# Current_measurement.net
KiCad netlist of a schematic drawn in Altium Designer
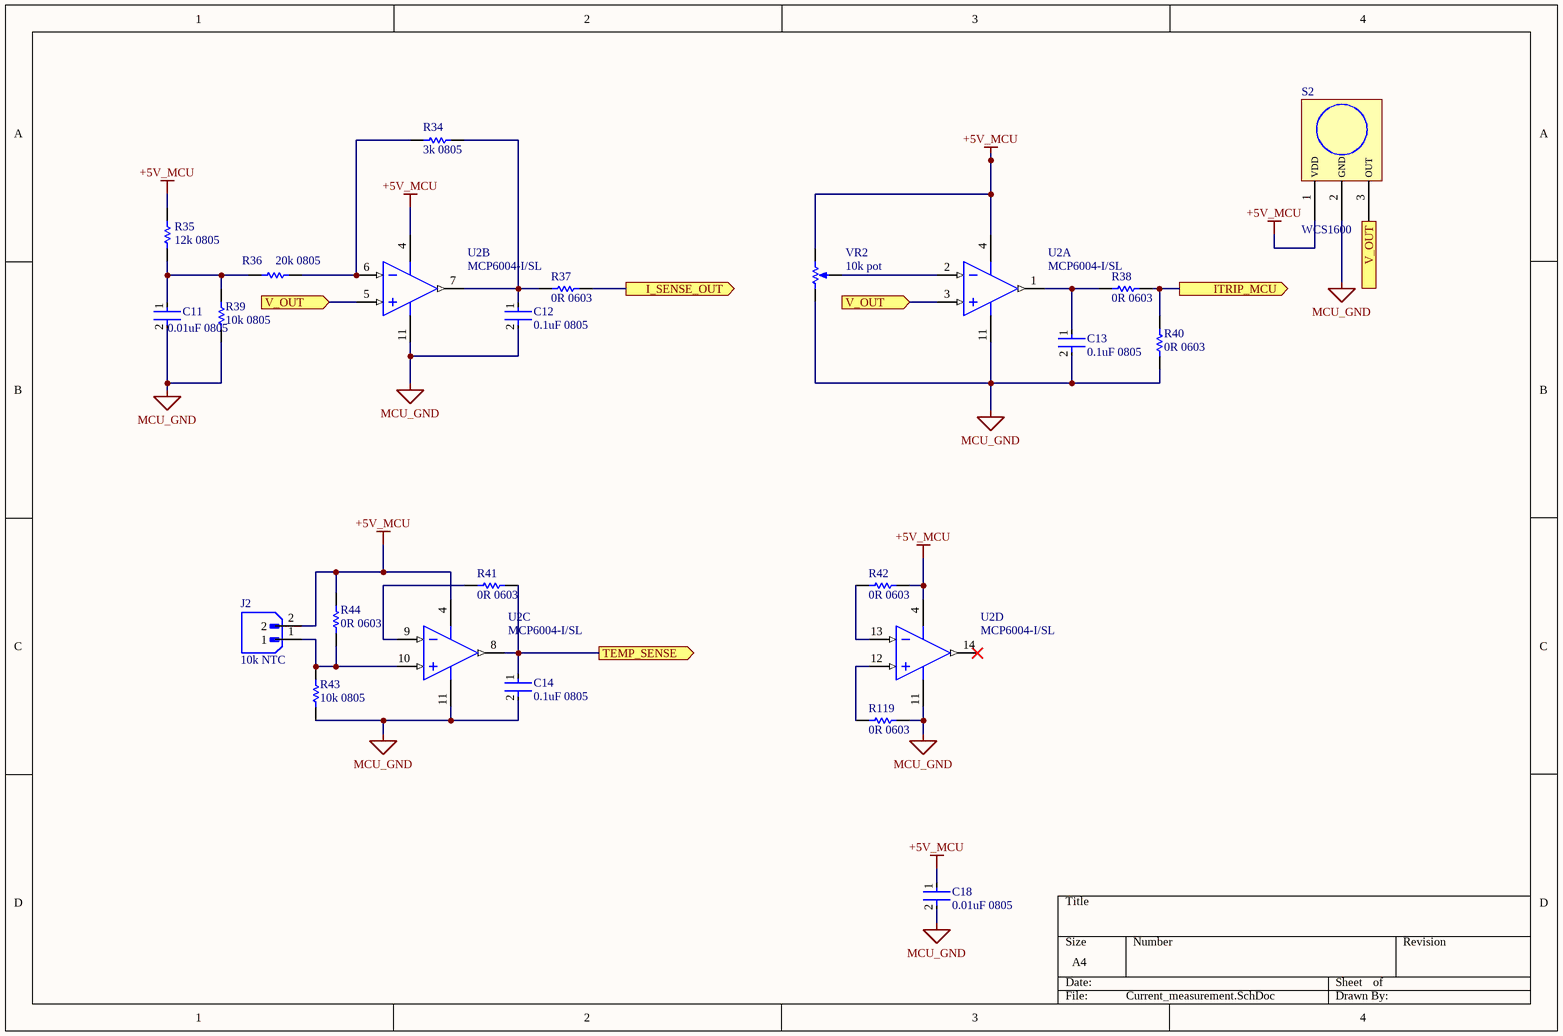
[diagram p0: Current_measurement.SchDoc]

(export (version "E")
  (design (tool "Eeschema 10.0.6"))
  (components
    (comp (ref "C11")
      (value "0.01uF 0805")
      (footprint "R0805")
      (description "10nF/0.01uF 50V Capacitor ±10% Tolerance 0805B103K500CT – 0805 Package")
      (libsource (lib "1kW_BLDC_Controller") (part "0.01uF 0805"))
    )
    (comp (ref "C12")
      (value "0.1uF 0805")
      (footprint "R0805")
      (description "0.1uF/100nF 100V Capacitor ±10% Tolerance CC0805KKX7R0BB104 – 0805 Package")
      (libsource (lib "1kW_BLDC_Controller") (part "0.1uF 0805"))
    )
    (comp (ref "C13")
      (value "0.1uF 0805")
      (footprint "R0805")
      (description "0.1uF/100nF 100V Capacitor ±10% Tolerance CC0805KKX7R0BB104 – 0805 Package")
      (libsource (lib "1kW_BLDC_Controller") (part "0.1uF 0805"))
    )
    (comp (ref "C14")
      (value "0.1uF 0805")
      (footprint "R0805")
      (description "0.1uF/100nF 100V Capacitor ±10% Tolerance CC0805KKX7R0BB104 – 0805 Package")
      (libsource (lib "1kW_BLDC_Controller") (part "0.1uF 0805"))
    )
    (comp (ref "C18")
      (value "0.01uF 0805")
      (footprint "R0805")
      (description "10nF/0.01uF 50V Capacitor ±10% Tolerance 0805B103K500CT – 0805 Package")
      (libsource (lib "1kW_BLDC_Controller") (part "0.01uF 0805"))
    )
    (comp (ref "J2")
      (value "10k NTC")
      (footprint "XH2.5-2p")
      (description "2 Pin JST-XH Male Straight 2515 Connector 2.54mm Pitch")
      (libsource (lib "1kW_BLDC_Controller_1") (part "XH2.5-2p"))
    )
    (comp (ref "R34")
      (value "3k 0805")
      (footprint "R0805")
      (description "3K Ohm 1/8 Watt Resistor 1% Tolerance 0805W8F3001T5E – 0805 Package")
      (libsource (lib "1kW_BLDC_Controller") (part "R0805"))
    )
    (comp (ref "R35")
      (value "12k 0805")
      (footprint "R0805")
      (description "12K Ohm 1/8 Watt Resistor 1% Tolerance RC0805FR-0712KL – 0805 Package")
      (libsource (lib "1kW_BLDC_Controller") (part "R0805"))
    )
    (comp (ref "R36")
      (value "20k 0805")
      (footprint "R0805")
      (description "20K ohm 1/8 Watt SMD Resistor 1% Tolerance RC0805FR-0720KL – 0805 Package")
      (libsource (lib "1kW_BLDC_Controller") (part "R0805"))
    )
    (comp (ref "R37")
      (value "0R 0603")
      (footprint "R0603")
      (description "0 Ohm 1/10 Watt Resistor 1% Tolerance RC0603FR-070RL – 0603 Package")
      (libsource (lib "1kW_BLDC_Controller") (part "R0000 0603"))
    )
    (comp (ref "R38")
      (value "0R 0603")
      (footprint "R0603")
      (description "0 Ohm 1/10 Watt Resistor 1% Tolerance RC0603FR-070RL – 0603 Package")
      (libsource (lib "1kW_BLDC_Controller") (part "R0000 0603"))
    )
    (comp (ref "R39")
      (value "10k 0805")
      (footprint "R0805")
      (description "10K Ohm 1/8 Watt Resistor 1% Tolerance RC0805FR-0710KL – 0805 Package")
      (libsource (lib "1kW_BLDC_Controller") (part "10k 0805"))
    )
    (comp (ref "R40")
      (value "0R 0603")
      (footprint "R0603")
      (description "0 Ohm 1/10 Watt Resistor 1% Tolerance RC0603FR-070RL – 0603 Package")
      (libsource (lib "1kW_BLDC_Controller") (part "R0000 0603"))
    )
    (comp (ref "R41")
      (value "0R 0603")
      (footprint "R0603")
      (description "0 Ohm 1/10 Watt Resistor 1% Tolerance RC0603FR-070RL – 0603 Package")
      (libsource (lib "1kW_BLDC_Controller") (part "R0000 0603"))
    )
    (comp (ref "R42")
      (value "0R 0603")
      (footprint "R0603")
      (description "0 Ohm 1/10 Watt Resistor 1% Tolerance RC0603FR-070RL – 0603 Package")
      (libsource (lib "1kW_BLDC_Controller") (part "R0000 0603"))
    )
    (comp (ref "R43")
      (value "10k 0805")
      (footprint "R0805")
      (description "10K Ohm 1/8 Watt Resistor 1% Tolerance RC0805FR-0710KL – 0805 Package")
      (libsource (lib "1kW_BLDC_Controller") (part "10k 0805"))
    )
    (comp (ref "R44")
      (value "0R 0603")
      (footprint "R0603")
      (description "0 Ohm 1/10 Watt Resistor 1% Tolerance RC0603FR-070RL – 0603 Package")
      (libsource (lib "1kW_BLDC_Controller") (part "R0000 0603"))
    )
    (comp (ref "R119")
      (value "0R 0603")
      (footprint "R0603")
      (description "0 Ohm 1/10 Watt Resistor 1% Tolerance RC0603FR-070RL – 0603 Package")
      (libsource (lib "1kW_BLDC_Controller") (part "R0000 0603"))
    )
    (comp (ref "S2")
      (value "WCS1600")
      (footprint "WCS1600")
      (description "WCS1600 100A Hall Effect Linear Current Sensor")
      (libsource (lib "1kW_BLDC_Controller") (part "WCS1600"))
    )
    (comp (ref "U2")
      (value "MCP6004-I/SL")
      (footprint "SOIC-SL14_M")
      (description "MCP6004 1MHz Rail-to-Rail Operational Amplifier – SOIC-14 Package")
      (libsource (lib "Altium Content Vault") (part "AMP-OPA-MCP6004-IL14"))
    )
    (comp (ref "VR2")
      (value "10k pot")
      (footprint "BOUR-3299W-3_V")
      (description "10K ohm Variable Resistor-Trimpot 3296 Package")
      (fields (field (name "TOLERANCE") "10%") (field (name "MANUFACTURER") "Bourns"))
      (libsource (lib "Altium Content Vault") (part "BOUR-3299X-3"))
    )
  )
  (nets
    (net (code "1") (name "+5V_MCU") (class "Default")
      (node (ref "C18") (pin "1") (pinfunction "1_1") (pintype "passive"))
      (node (ref "J2") (pin "2") (pinfunction "2_2") (pintype "passive"))
      (node (ref "R35") (pin "2") (pinfunction "2_2") (pintype "passive"))
      (node (ref "R42") (pin "2") (pinfunction "2_2") (pintype "passive"))
      (node (ref "R44") (pin "2") (pinfunction "2_2") (pintype "passive"))
      (node (ref "S2") (pin "1") (pinfunction "VDD_1") (pintype "power_in"))
      (node (ref "U2") (pin "4") (pinfunction "VDD_4") (pintype "power_in"))
      (node (ref "VR2") (pin "1") (pinfunction "CCW_1") (pintype "passive"))
    )
    (net (code "2") (name "/ITRIP_MCU") (class "Default")
      (node (ref "R38") (pin "2") (pinfunction "2_2") (pintype "passive"))
      (node (ref "R40") (pin "2") (pinfunction "2_2") (pintype "passive"))
    )
    (net (code "3") (name "/I_SENSE_OUT") (class "Default")
      (node (ref "R37") (pin "2") (pinfunction "2_2") (pintype "passive"))
    )
    (net (code "4") (name "/TEMP_SENSE") (class "Default")
      (node (ref "C14") (pin "1") (pinfunction "1_1") (pintype "passive"))
      (node (ref "R41") (pin "2") (pinfunction "2_2") (pintype "passive"))
      (node (ref "U2") (pin "8") (pinfunction "VOUTC_8") (pintype "output"))
    )
    (net (code "5") (name "/V_OUT") (class "Default")
      (node (ref "S2") (pin "3") (pinfunction "OUT_3") (pintype "passive"))
      (node (ref "U2") (pin "3") (pinfunction "VINA+_3") (pintype "input"))
      (node (ref "U2") (pin "5") (pinfunction "VINB+_5") (pintype "input"))
    )
    (net (code "6") (name "MCU_GND") (class "Default")
      (node (ref "C11") (pin "2") (pinfunction "2_2") (pintype "passive"))
      (node (ref "C12") (pin "2") (pinfunction "2_2") (pintype "passive"))
      (node (ref "C13") (pin "2") (pinfunction "2_2") (pintype "passive"))
      (node (ref "C14") (pin "2") (pinfunction "2_2") (pintype "passive"))
      (node (ref "C18") (pin "2") (pinfunction "2_2") (pintype "passive"))
      (node (ref "R119") (pin "2") (pinfunction "2_2") (pintype "passive"))
      (node (ref "R39") (pin "1") (pinfunction "1_1") (pintype "passive"))
      (node (ref "R40") (pin "1") (pinfunction "1_1") (pintype "passive"))
      (node (ref "R43") (pin "1") (pinfunction "1_1") (pintype "passive"))
      (node (ref "S2") (pin "2") (pinfunction "GND_2") (pintype "power_in"))
      (node (ref "U2") (pin "11") (pinfunction "VSS_11") (pintype "power_in"))
      (node (ref "VR2") (pin "3") (pinfunction "CW_3") (pintype "passive"))
    )
    (net (code "7") (name "Net-(C11-Pad1)") (class "Default")
      (node (ref "C11") (pin "1") (pinfunction "1_1") (pintype "passive"))
      (node (ref "R35") (pin "1") (pinfunction "1_1") (pintype "passive"))
      (node (ref "R36") (pin "1") (pinfunction "1_1") (pintype "passive"))
      (node (ref "R39") (pin "2") (pinfunction "2_2") (pintype "passive"))
    )
    (net (code "8") (name "Net-(U2A-VINA-)") (class "Default")
      (node (ref "U2") (pin "2") (pinfunction "VINA-_2") (pintype "input"))
      (node (ref "VR2") (pin "2") (pinfunction "WIPER_2") (pintype "passive"))
    )
    (net (code "9") (name "Net-(U2A-VOUTA)") (class "Default")
      (node (ref "C13") (pin "1") (pinfunction "1_1") (pintype "passive"))
      (node (ref "R38") (pin "1") (pinfunction "1_1") (pintype "passive"))
      (node (ref "U2") (pin "1") (pinfunction "VOUTA_1") (pintype "output"))
    )
    (net (code "10") (name "Net-(U2B-VINB-)") (class "Default")
      (node (ref "R34") (pin "1") (pinfunction "1_1") (pintype "passive"))
      (node (ref "R36") (pin "2") (pinfunction "2_2") (pintype "passive"))
      (node (ref "U2") (pin "6") (pinfunction "VINB-_6") (pintype "input"))
    )
    (net (code "11") (name "Net-(U2B-VOUTB)") (class "Default")
      (node (ref "C12") (pin "1") (pinfunction "1_1") (pintype "passive"))
      (node (ref "R34") (pin "2") (pinfunction "2_2") (pintype "passive"))
      (node (ref "R37") (pin "1") (pinfunction "1_1") (pintype "passive"))
      (node (ref "U2") (pin "7") (pinfunction "VOUTB_7") (pintype "output"))
    )
    (net (code "12") (name "Net-(U2C-VINC+)") (class "Default")
      (node (ref "J2") (pin "1") (pinfunction "1_1") (pintype "passive"))
      (node (ref "R43") (pin "2") (pinfunction "2_2") (pintype "passive"))
      (node (ref "R44") (pin "1") (pinfunction "1_1") (pintype "passive"))
      (node (ref "U2") (pin "10") (pinfunction "VINC+_10") (pintype "input"))
    )
    (net (code "13") (name "Net-(U2C-VINC-)") (class "Default")
      (node (ref "R41") (pin "1") (pinfunction "1_1") (pintype "passive"))
      (node (ref "U2") (pin "9") (pinfunction "VINC-_9") (pintype "input"))
    )
    (net (code "14") (name "Net-(U2D-VIND+)") (class "Default")
      (node (ref "R119") (pin "1") (pinfunction "1_1") (pintype "passive"))
      (node (ref "U2") (pin "12") (pinfunction "VIND+_12") (pintype "input"))
    )
    (net (code "15") (name "Net-(U2D-VIND-)") (class "Default")
      (node (ref "R42") (pin "1") (pinfunction "1_1") (pintype "passive"))
      (node (ref "U2") (pin "13") (pinfunction "VIND-_13") (pintype "input"))
    )
    (net (code "16") (name "unconnected-(U2D-VOUTD-Pad14)") (class "Default")
      (node (ref "U2") (pin "14") (pinfunction "VOUTD_14") (pintype "output+no_connect"))
    )
  )
)
